# Behavioural_board_V2.net
KiCad netlist of a schematic drawn in EAGLE
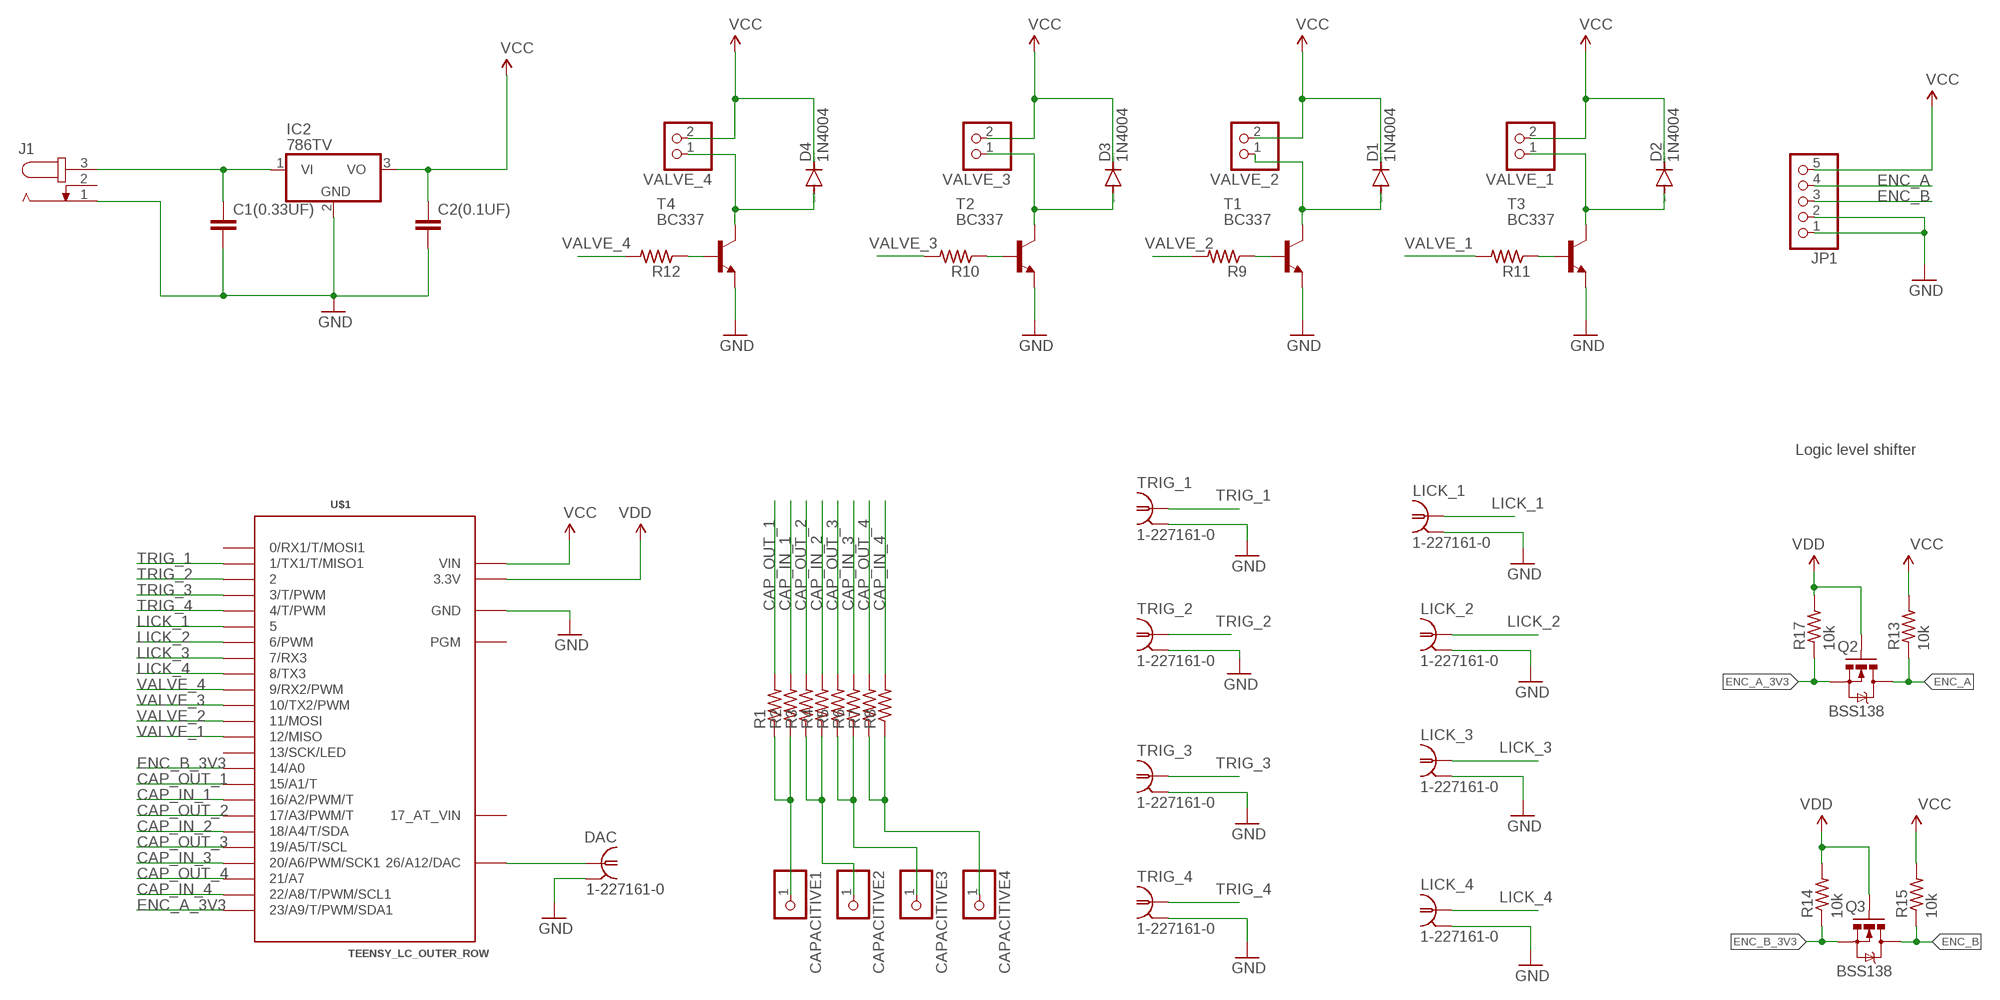
[diagram p0: schematic, sheet 1]

(export (version "E")
  (design (tool "Eeschema 10.0.6"))
  (components
    (comp (ref "C1(0.33UF)")
      (value "C2.5/4")
      (footprint "eagle-import:C2.5-4")
      (libsource (lib "eagle-import") (part "C2.5/4"))
    )
    (comp (ref "C2(0.1UF)")
      (value "C2.5/2")
      (footprint "eagle-import:C2.5-2")
      (libsource (lib "eagle-import") (part "C2.5/2"))
    )
    (comp (ref "CAPACITIVE1")
      (value "PINHD-1X1")
      (footprint "eagle-import:1X01")
      (libsource (lib "eagle-import") (part "PINHD-1X1"))
    )
    (comp (ref "CAPACITIVE2")
      (value "PINHD-1X1")
      (footprint "eagle-import:1X01")
      (libsource (lib "eagle-import") (part "PINHD-1X1"))
    )
    (comp (ref "CAPACITIVE3")
      (value "PINHD-1X1")
      (footprint "eagle-import:1X01")
      (libsource (lib "eagle-import") (part "PINHD-1X1"))
    )
    (comp (ref "CAPACITIVE4")
      (value "PINHD-1X1")
      (footprint "eagle-import:1X01")
      (libsource (lib "eagle-import") (part "PINHD-1X1"))
    )
    (comp (ref "D1")
      (value "1N4004")
      (footprint "eagle-import:DO41-10")
      (libsource (lib "eagle-import") (part "1N4004"))
    )
    (comp (ref "D2")
      (value "1N4004")
      (footprint "eagle-import:DO41-10")
      (libsource (lib "eagle-import") (part "1N4004"))
    )
    (comp (ref "D3")
      (value "1N4004")
      (footprint "eagle-import:DO41-10")
      (libsource (lib "eagle-import") (part "1N4004"))
    )
    (comp (ref "D4")
      (value "1N4004")
      (footprint "eagle-import:DO41-10")
      (libsource (lib "eagle-import") (part "1N4004"))
    )
    (comp (ref "DAC")
      (value "1-227161-0")
      (footprint "eagle-import:AMP_227161")
      (fields (field (name "MF") "TYCO ELECTRONICS") (field (name "MPN") "1-227161"))
      (libsource (lib "eagle-import") (part "?2271611--0"))
    )
    (comp (ref "IC2")
      (value "786TV")
      (footprint "eagle-import:TO220V")
      (libsource (lib "eagle-import") (part "78TV6"))
    )
    (comp (ref "J1")
      (value "JACK-PLUG0")
      (footprint "eagle-import:SPC4077")
      (libsource (lib "eagle-import") (part "JACK-PLUG0"))
    )
    (comp (ref "JP1")
      (value "PINHD-1X5")
      (footprint "eagle-import:1X05")
      (libsource (lib "eagle-import") (part "PINHD-1X5"))
    )
    (comp (ref "LICK_1")
      (value "1-227161-0")
      (footprint "eagle-import:AMP_227161")
      (fields (field (name "MF") "TYCO ELECTRONICS") (field (name "MPN") "1-227161"))
      (libsource (lib "eagle-import") (part "?2271611--0"))
    )
    (comp (ref "LICK_2")
      (value "1-227161-0")
      (footprint "eagle-import:AMP_227161")
      (fields (field (name "MF") "TYCO ELECTRONICS") (field (name "MPN") "1-227161"))
      (libsource (lib "eagle-import") (part "?2271611--0"))
    )
    (comp (ref "LICK_3")
      (value "1-227161-0")
      (footprint "eagle-import:AMP_227161")
      (fields (field (name "MF") "TYCO ELECTRONICS") (field (name "MPN") "1-227161"))
      (libsource (lib "eagle-import") (part "?2271611--0"))
    )
    (comp (ref "LICK_4")
      (value "1-227161-0")
      (footprint "eagle-import:AMP_227161")
      (fields (field (name "MF") "TYCO ELECTRONICS") (field (name "MPN") "1-227161"))
      (libsource (lib "eagle-import") (part "?2271611--0"))
    )
    (comp (ref "Q2")
      (value "BSS138")
      (footprint "eagle-import:SOT23-3")
      (libsource (lib "eagle-import") (part "MOSFET-NCHANNELSMD"))
    )
    (comp (ref "Q3")
      (value "BSS138")
      (footprint "eagle-import:SOT23-3")
      (libsource (lib "eagle-import") (part "MOSFET-NCHANNELSMD"))
    )
    (comp (ref "R1")
      (value "R-US_0207/10")
      (footprint "eagle-import:0207_10")
      (libsource (lib "eagle-import") (part "R-US_0207/10"))
    )
    (comp (ref "R2")
      (value "R-US_0207/10")
      (footprint "eagle-import:0207_10")
      (libsource (lib "eagle-import") (part "R-US_0207/10"))
    )
    (comp (ref "R3")
      (value "R-US_0207/10")
      (footprint "eagle-import:0207_10")
      (libsource (lib "eagle-import") (part "R-US_0207/10"))
    )
    (comp (ref "R4")
      (value "R-US_0207/10")
      (footprint "eagle-import:0207_10")
      (libsource (lib "eagle-import") (part "R-US_0207/10"))
    )
    (comp (ref "R5")
      (value "R-US_0207/10")
      (footprint "eagle-import:0207_10")
      (libsource (lib "eagle-import") (part "R-US_0207/10"))
    )
    (comp (ref "R6")
      (value "R-US_0207/10")
      (footprint "eagle-import:0207_10")
      (libsource (lib "eagle-import") (part "R-US_0207/10"))
    )
    (comp (ref "R7")
      (value "R-US_0207/10")
      (footprint "eagle-import:0207_10")
      (libsource (lib "eagle-import") (part "R-US_0207/10"))
    )
    (comp (ref "R8")
      (value "R-US_0207/10")
      (footprint "eagle-import:0207_10")
      (libsource (lib "eagle-import") (part "R-US_0207/10"))
    )
    (comp (ref "R9")
      (value "R-US_0207/10")
      (footprint "eagle-import:0207_10")
      (libsource (lib "eagle-import") (part "R-US_0207/10"))
    )
    (comp (ref "R10")
      (value "R-US_0207/10")
      (footprint "eagle-import:0207_10")
      (libsource (lib "eagle-import") (part "R-US_0207/10"))
    )
    (comp (ref "R11")
      (value "R-US_0207/10")
      (footprint "eagle-import:0207_10")
      (libsource (lib "eagle-import") (part "R-US_0207/10"))
    )
    (comp (ref "R12")
      (value "R-US_0207/10")
      (footprint "eagle-import:0207_10")
      (libsource (lib "eagle-import") (part "R-US_0207/10"))
    )
    (comp (ref "R13")
      (value "10k")
      (footprint "eagle-import:0207_10")
      (libsource (lib "eagle-import") (part "R-US_0207/10"))
    )
    (comp (ref "R14")
      (value "10k")
      (footprint "eagle-import:0207_10")
      (libsource (lib "eagle-import") (part "R-US_0207/10"))
    )
    (comp (ref "R15")
      (value "10k")
      (footprint "eagle-import:0207_10")
      (libsource (lib "eagle-import") (part "R-US_0207/10"))
    )
    (comp (ref "R17")
      (value "10k")
      (footprint "eagle-import:0207_10")
      (libsource (lib "eagle-import") (part "R-US_0207/10"))
    )
    (comp (ref "T1")
      (value "BC337")
      (footprint "eagle-import:TO92")
      (libsource (lib "eagle-import") (part "BC337"))
    )
    (comp (ref "T2")
      (value "BC337")
      (footprint "eagle-import:TO92")
      (libsource (lib "eagle-import") (part "BC337"))
    )
    (comp (ref "T3")
      (value "BC337")
      (footprint "eagle-import:TO92")
      (libsource (lib "eagle-import") (part "BC337"))
    )
    (comp (ref "T4")
      (value "BC337")
      (footprint "eagle-import:TO92")
      (libsource (lib "eagle-import") (part "BC337"))
    )
    (comp (ref "TRIG_1")
      (value "1-227161-0")
      (footprint "eagle-import:AMP_227161")
      (fields (field (name "MF") "TYCO ELECTRONICS") (field (name "MPN") "1-227161"))
      (libsource (lib "eagle-import") (part "?2271611--0"))
    )
    (comp (ref "TRIG_2")
      (value "1-227161-0")
      (footprint "eagle-import:AMP_227161")
      (fields (field (name "MF") "TYCO ELECTRONICS") (field (name "MPN") "1-227161"))
      (libsource (lib "eagle-import") (part "?2271611--0"))
    )
    (comp (ref "TRIG_3")
      (value "1-227161-0")
      (footprint "eagle-import:AMP_227161")
      (fields (field (name "MF") "TYCO ELECTRONICS") (field (name "MPN") "1-227161"))
      (libsource (lib "eagle-import") (part "?2271611--0"))
    )
    (comp (ref "TRIG_4")
      (value "1-227161-0")
      (footprint "eagle-import:AMP_227161")
      (fields (field (name "MF") "TYCO ELECTRONICS") (field (name "MPN") "1-227161"))
      (libsource (lib "eagle-import") (part "?2271611--0"))
    )
    (comp (ref "U$1")
      (value "TEENSY_LC_OUTER_ROW")
      (footprint "eagle-import:TEENSY_3.0-3.2&LC_OUTER_ROW")
      (libsource (lib "eagle-import") (part "TEENSY_LC_OUTER_ROW"))
    )
    (comp (ref "VALVE_1")
      (value "PINHD-1X2")
      (footprint "eagle-import:1X02")
      (libsource (lib "eagle-import") (part "PINHD-1X2"))
    )
    (comp (ref "VALVE_2")
      (value "PINHD-1X2")
      (footprint "eagle-import:1X02")
      (libsource (lib "eagle-import") (part "PINHD-1X2"))
    )
    (comp (ref "VALVE_3")
      (value "PINHD-1X2")
      (footprint "eagle-import:1X02")
      (libsource (lib "eagle-import") (part "PINHD-1X2"))
    )
    (comp (ref "VALVE_4")
      (value "PINHD-1X2")
      (footprint "eagle-import:1X02")
      (libsource (lib "eagle-import") (part "PINHD-1X2"))
    )
  )
  (nets
    (net (code "1") (name "/CAP_IN_1") (class "Default")
      (node (ref "R2") (pin "2") (pinfunction "2_2") (pintype "passive"))
      (node (ref "U$1") (pin "16/A2") (pinfunction "16/A2/PWM/T_16/A2") (pintype "bidirectional"))
    )
    (net (code "2") (name "/CAP_IN_2") (class "Default")
      (node (ref "R4") (pin "2") (pinfunction "2_2") (pintype "passive"))
      (node (ref "U$1") (pin "18/A4") (pinfunction "18/A4/T/SDA_18/A4") (pintype "bidirectional"))
    )
    (net (code "3") (name "/CAP_IN_3") (class "Default")
      (node (ref "R6") (pin "2") (pinfunction "2_2") (pintype "passive"))
      (node (ref "U$1") (pin "20/A6") (pinfunction "20/A6/PWM/SCK1_20/A6") (pintype "bidirectional"))
    )
    (net (code "4") (name "/CAP_IN_4") (class "Default")
      (node (ref "R8") (pin "2") (pinfunction "2_2") (pintype "passive"))
      (node (ref "U$1") (pin "22/A8") (pinfunction "22/A8/T/PWM/SCL1_22/A8") (pintype "bidirectional"))
    )
    (net (code "5") (name "/CAP_OUT_1") (class "Default")
      (node (ref "R1") (pin "2") (pinfunction "2_2") (pintype "passive"))
      (node (ref "U$1") (pin "15/A1") (pinfunction "15/A1/T_15/A1") (pintype "bidirectional"))
    )
    (net (code "6") (name "/CAP_OUT_2") (class "Default")
      (node (ref "R3") (pin "2") (pinfunction "2_2") (pintype "passive"))
      (node (ref "U$1") (pin "17/A3") (pinfunction "17/A3/PWM/T_17/A3") (pintype "bidirectional"))
    )
    (net (code "7") (name "/CAP_OUT_3") (class "Default")
      (node (ref "R5") (pin "2") (pinfunction "2_2") (pintype "passive"))
      (node (ref "U$1") (pin "19/A5") (pinfunction "19/A5/T/SCL_19/A5") (pintype "bidirectional"))
    )
    (net (code "8") (name "/CAP_OUT_4") (class "Default")
      (node (ref "R7") (pin "2") (pinfunction "2_2") (pintype "passive"))
      (node (ref "U$1") (pin "21/A7") (pinfunction "21/A7_21/A7") (pintype "bidirectional"))
    )
    (net (code "9") (name "/LICK_1") (class "Default")
      (node (ref "LICK_1") (pin "1") (pinfunction "1_1") (pintype "passive"))
      (node (ref "U$1") (pin "5") (pinfunction "5_5") (pintype "bidirectional"))
    )
    (net (code "10") (name "/LICK_2") (class "Default")
      (node (ref "LICK_2") (pin "1") (pinfunction "1_1") (pintype "passive"))
      (node (ref "U$1") (pin "6") (pinfunction "6/PWM_6") (pintype "bidirectional"))
    )
    (net (code "11") (name "/LICK_3") (class "Default")
      (node (ref "LICK_3") (pin "1") (pinfunction "1_1") (pintype "passive"))
      (node (ref "U$1") (pin "7") (pinfunction "7/RX3_7") (pintype "bidirectional"))
    )
    (net (code "12") (name "/LICK_4") (class "Default")
      (node (ref "LICK_4") (pin "1") (pinfunction "1_1") (pintype "passive"))
      (node (ref "U$1") (pin "8") (pinfunction "8/TX3_8") (pintype "bidirectional"))
    )
    (net (code "13") (name "/TRIG_1") (class "Default")
      (node (ref "TRIG_1") (pin "1") (pinfunction "1_1") (pintype "passive"))
      (node (ref "U$1") (pin "1") (pinfunction "1/TX1/T/MISO1_1") (pintype "bidirectional"))
    )
    (net (code "14") (name "/TRIG_2") (class "Default")
      (node (ref "TRIG_2") (pin "1") (pinfunction "1_1") (pintype "passive"))
      (node (ref "U$1") (pin "2") (pinfunction "2_2") (pintype "bidirectional"))
    )
    (net (code "15") (name "/TRIG_3") (class "Default")
      (node (ref "TRIG_3") (pin "1") (pinfunction "1_1") (pintype "passive"))
      (node (ref "U$1") (pin "3") (pinfunction "3/T/PWM_3") (pintype "bidirectional"))
    )
    (net (code "16") (name "/TRIG_4") (class "Default")
      (node (ref "TRIG_4") (pin "1") (pinfunction "1_1") (pintype "passive"))
      (node (ref "U$1") (pin "4") (pinfunction "4/T/PWM_4") (pintype "bidirectional"))
    )
    (net (code "17") (name "/VALVE_1") (class "Default")
      (node (ref "R11") (pin "2") (pinfunction "2_2") (pintype "passive"))
      (node (ref "U$1") (pin "12") (pinfunction "12/MISO_12") (pintype "bidirectional"))
    )
    (net (code "18") (name "/VALVE_2") (class "Default")
      (node (ref "R9") (pin "2") (pinfunction "2_2") (pintype "passive"))
      (node (ref "U$1") (pin "11") (pinfunction "11/MOSI_11") (pintype "bidirectional"))
    )
    (net (code "19") (name "/VALVE_3") (class "Default")
      (node (ref "R10") (pin "2") (pinfunction "2_2") (pintype "passive"))
      (node (ref "U$1") (pin "10") (pinfunction "10/TX2/PWM_10") (pintype "bidirectional"))
    )
    (net (code "20") (name "/VALVE_4") (class "Default")
      (node (ref "R12") (pin "2") (pinfunction "2_2") (pintype "passive"))
      (node (ref "U$1") (pin "9") (pinfunction "9/RX2/PWM_9") (pintype "bidirectional"))
    )
    (net (code "21") (name "ENC_A") (class "Default")
      (node (ref "JP1") (pin "4") (pinfunction "4_4") (pintype "passive"))
      (node (ref "Q2") (pin "3") (pinfunction "D_3") (pintype "passive"))
      (node (ref "R13") (pin "1") (pinfunction "1_1") (pintype "passive"))
    )
    (net (code "22") (name "ENC_A_3V3") (class "Default")
      (node (ref "Q2") (pin "2") (pinfunction "S_2") (pintype "passive"))
      (node (ref "R17") (pin "1") (pinfunction "1_1") (pintype "passive"))
      (node (ref "U$1") (pin "23/A9") (pinfunction "23/A9/T/PWM/SDA1_23/A9") (pintype "bidirectional"))
    )
    (net (code "23") (name "ENC_B") (class "Default")
      (node (ref "JP1") (pin "3") (pinfunction "3_3") (pintype "passive"))
      (node (ref "Q3") (pin "3") (pinfunction "D_3") (pintype "passive"))
      (node (ref "R15") (pin "1") (pinfunction "1_1") (pintype "passive"))
    )
    (net (code "24") (name "ENC_B_3V3") (class "Default")
      (node (ref "Q3") (pin "2") (pinfunction "S_2") (pintype "passive"))
      (node (ref "R14") (pin "1") (pinfunction "1_1") (pintype "passive"))
      (node (ref "U$1") (pin "14/A0") (pinfunction "14/A0_14/A0") (pintype "bidirectional"))
    )
    (net (code "25") (name "GND") (class "Default")
      (node (ref "C1(0.33UF)") (pin "2") (pinfunction "2_2") (pintype "passive"))
      (node (ref "C2(0.1UF)") (pin "2") (pinfunction "2_2") (pintype "passive"))
      (node (ref "DAC") (pin "2") (pinfunction "2_2") (pintype "passive"))
      (node (ref "IC2") (pin "2") (pinfunction "GND_2") (pintype "passive"))
      (node (ref "J1") (pin "1") (pinfunction "1_1") (pintype "passive"))
      (node (ref "JP1") (pin "1") (pinfunction "1_1") (pintype "passive"))
      (node (ref "JP1") (pin "2") (pinfunction "2_2") (pintype "passive"))
      (node (ref "LICK_1") (pin "2") (pinfunction "2_2") (pintype "passive"))
      (node (ref "LICK_2") (pin "2") (pinfunction "2_2") (pintype "passive"))
      (node (ref "LICK_3") (pin "2") (pinfunction "2_2") (pintype "passive"))
      (node (ref "LICK_4") (pin "2") (pinfunction "2_2") (pintype "passive"))
      (node (ref "T1") (pin "1") (pinfunction "E_1") (pintype "passive"))
      (node (ref "T2") (pin "1") (pinfunction "E_1") (pintype "passive"))
      (node (ref "T3") (pin "1") (pinfunction "E_1") (pintype "passive"))
      (node (ref "T4") (pin "1") (pinfunction "E_1") (pintype "passive"))
      (node (ref "TRIG_1") (pin "2") (pinfunction "2_2") (pintype "passive"))
      (node (ref "TRIG_2") (pin "2") (pinfunction "2_2") (pintype "passive"))
      (node (ref "TRIG_3") (pin "2") (pinfunction "2_2") (pintype "passive"))
      (node (ref "TRIG_4") (pin "2") (pinfunction "2_2") (pintype "passive"))
      (node (ref "U$1") (pin "AGND") (pinfunction "GND_AGND") (pintype "power_in"))
      (node (ref "U$1") (pin "GND") (pinfunction "GND_GND") (pintype "power_in"))
      (node (ref "U$1") (pin "GND1") (pinfunction "GND_GND1") (pintype "power_in"))
    )
    (net (code "26") (name "Net-(CAPACITIVE1-Pad1)") (class "Default")
      (node (ref "CAPACITIVE1") (pin "1") (pinfunction "1_1") (pintype "passive"))
      (node (ref "R1") (pin "1") (pinfunction "1_1") (pintype "passive"))
      (node (ref "R2") (pin "1") (pinfunction "1_1") (pintype "passive"))
    )
    (net (code "27") (name "Net-(CAPACITIVE2-Pad1)") (class "Default")
      (node (ref "CAPACITIVE2") (pin "1") (pinfunction "1_1") (pintype "passive"))
      (node (ref "R3") (pin "1") (pinfunction "1_1") (pintype "passive"))
      (node (ref "R4") (pin "1") (pinfunction "1_1") (pintype "passive"))
    )
    (net (code "28") (name "Net-(CAPACITIVE3-Pad1)") (class "Default")
      (node (ref "CAPACITIVE3") (pin "1") (pinfunction "1_1") (pintype "passive"))
      (node (ref "R5") (pin "1") (pinfunction "1_1") (pintype "passive"))
      (node (ref "R6") (pin "1") (pinfunction "1_1") (pintype "passive"))
    )
    (net (code "29") (name "Net-(CAPACITIVE4-Pad1)") (class "Default")
      (node (ref "CAPACITIVE4") (pin "1") (pinfunction "1_1") (pintype "passive"))
      (node (ref "R7") (pin "1") (pinfunction "1_1") (pintype "passive"))
      (node (ref "R8") (pin "1") (pinfunction "1_1") (pintype "passive"))
    )
    (net (code "30") (name "Net-(IC2-VI)") (class "Default")
      (node (ref "C1(0.33UF)") (pin "1") (pinfunction "1_1") (pintype "passive"))
      (node (ref "IC2") (pin "1") (pinfunction "VI_1") (pintype "input"))
      (node (ref "J1") (pin "3") (pinfunction "3_3") (pintype "passive"))
    )
    (net (code "31") (name "Net-(T1-B)") (class "Default")
      (node (ref "R9") (pin "1") (pinfunction "1_1") (pintype "passive"))
      (node (ref "T1") (pin "2") (pinfunction "B_2") (pintype "passive"))
    )
    (net (code "32") (name "Net-(T1-C)") (class "Default")
      (node (ref "D1") (pin "A") (pinfunction "A_A") (pintype "passive"))
      (node (ref "T1") (pin "3") (pinfunction "C_3") (pintype "passive"))
      (node (ref "VALVE_2") (pin "1") (pinfunction "1_1") (pintype "passive"))
    )
    (net (code "33") (name "Net-(T2-B)") (class "Default")
      (node (ref "R10") (pin "1") (pinfunction "1_1") (pintype "passive"))
      (node (ref "T2") (pin "2") (pinfunction "B_2") (pintype "passive"))
    )
    (net (code "34") (name "Net-(T2-C)") (class "Default")
      (node (ref "D3") (pin "A") (pinfunction "A_A") (pintype "passive"))
      (node (ref "T2") (pin "3") (pinfunction "C_3") (pintype "passive"))
      (node (ref "VALVE_3") (pin "1") (pinfunction "1_1") (pintype "passive"))
    )
    (net (code "35") (name "Net-(T3-B)") (class "Default")
      (node (ref "R11") (pin "1") (pinfunction "1_1") (pintype "passive"))
      (node (ref "T3") (pin "2") (pinfunction "B_2") (pintype "passive"))
    )
    (net (code "36") (name "Net-(T3-C)") (class "Default")
      (node (ref "D2") (pin "A") (pinfunction "A_A") (pintype "passive"))
      (node (ref "T3") (pin "3") (pinfunction "C_3") (pintype "passive"))
      (node (ref "VALVE_1") (pin "1") (pinfunction "1_1") (pintype "passive"))
    )
    (net (code "37") (name "Net-(T4-B)") (class "Default")
      (node (ref "R12") (pin "1") (pinfunction "1_1") (pintype "passive"))
      (node (ref "T4") (pin "2") (pinfunction "B_2") (pintype "passive"))
    )
    (net (code "38") (name "Net-(T4-C)") (class "Default")
      (node (ref "D4") (pin "A") (pinfunction "A_A") (pintype "passive"))
      (node (ref "T4") (pin "3") (pinfunction "C_3") (pintype "passive"))
      (node (ref "VALVE_4") (pin "1") (pinfunction "1_1") (pintype "passive"))
    )
    (net (code "39") (name "Net-(U$1-26{slash}A12{slash}DAC)") (class "Default")
      (node (ref "DAC") (pin "1") (pinfunction "1_1") (pintype "passive"))
      (node (ref "U$1") (pin "RESET/DAC") (pinfunction "26/A12/DAC_RESET/DAC") (pintype "power_in"))
    )
    (net (code "40") (name "VCC") (class "Default")
      (node (ref "C2(0.1UF)") (pin "1") (pinfunction "1_1") (pintype "passive"))
      (node (ref "D1") (pin "C") (pinfunction "C_C") (pintype "passive"))
      (node (ref "D2") (pin "C") (pinfunction "C_C") (pintype "passive"))
      (node (ref "D3") (pin "C") (pinfunction "C_C") (pintype "passive"))
      (node (ref "D4") (pin "C") (pinfunction "C_C") (pintype "passive"))
      (node (ref "IC2") (pin "3") (pinfunction "VO_3") (pintype "passive"))
      (node (ref "JP1") (pin "5") (pinfunction "5_5") (pintype "passive"))
      (node (ref "R13") (pin "2") (pinfunction "2_2") (pintype "passive"))
      (node (ref "R15") (pin "2") (pinfunction "2_2") (pintype "passive"))
      (node (ref "U$1") (pin "VIN") (pinfunction "VIN_VIN") (pintype "power_in"))
      (node (ref "VALVE_1") (pin "2") (pinfunction "2_2") (pintype "passive"))
      (node (ref "VALVE_2") (pin "2") (pinfunction "2_2") (pintype "passive"))
      (node (ref "VALVE_3") (pin "2") (pinfunction "2_2") (pintype "passive"))
      (node (ref "VALVE_4") (pin "2") (pinfunction "2_2") (pintype "passive"))
    )
    (net (code "41") (name "VDD") (class "Default")
      (node (ref "Q2") (pin "1") (pinfunction "G_1") (pintype "passive"))
      (node (ref "Q3") (pin "1") (pinfunction "G_1") (pintype "passive"))
      (node (ref "R14") (pin "2") (pinfunction "2_2") (pintype "passive"))
      (node (ref "R17") (pin "2") (pinfunction "2_2") (pintype "passive"))
      (node (ref "U$1") (pin "3.3V") (pinfunction "3.3V_3.3V") (pintype "power_in"))
      (node (ref "U$1") (pin "3.3V1") (pinfunction "3.3V_3.3V1") (pintype "power_in"))
    )
    (net (code "42") (name "unconnected-(J1-Pad2)") (class "Default")
      (node (ref "J1") (pin "2") (pinfunction "2_2") (pintype "passive"))
    )
    (net (code "43") (name "unconnected-(U$1-0{slash}RX1{slash}T{slash}MOSI1-Pad0)") (class "Default")
      (node (ref "U$1") (pin "0") (pinfunction "0/RX1/T/MOSI1_0") (pintype "bidirectional"))
    )
    (net (code "44") (name "unconnected-(U$1-13{slash}SCK{slash}LED-Pad13)") (class "Default")
      (node (ref "U$1") (pin "13") (pinfunction "13/SCK/LED_13") (pintype "bidirectional"))
    )
    (net (code "45") (name "unconnected-(U$1-17_AT_VIN-PadVBAT)") (class "Default")
      (node (ref "U$1") (pin "VBAT") (pinfunction "17_AT_VIN_VBAT") (pintype "bidirectional"))
    )
    (net (code "46") (name "unconnected-(U$1-PadPGM)") (class "Default")
      (node (ref "U$1") (pin "PGM") (pinfunction "PGM_PGM") (pintype "bidirectional"))
    )
  )
)
